# Transimpedance.net
KiCad netlist of a schematic drawn in Altium Designer
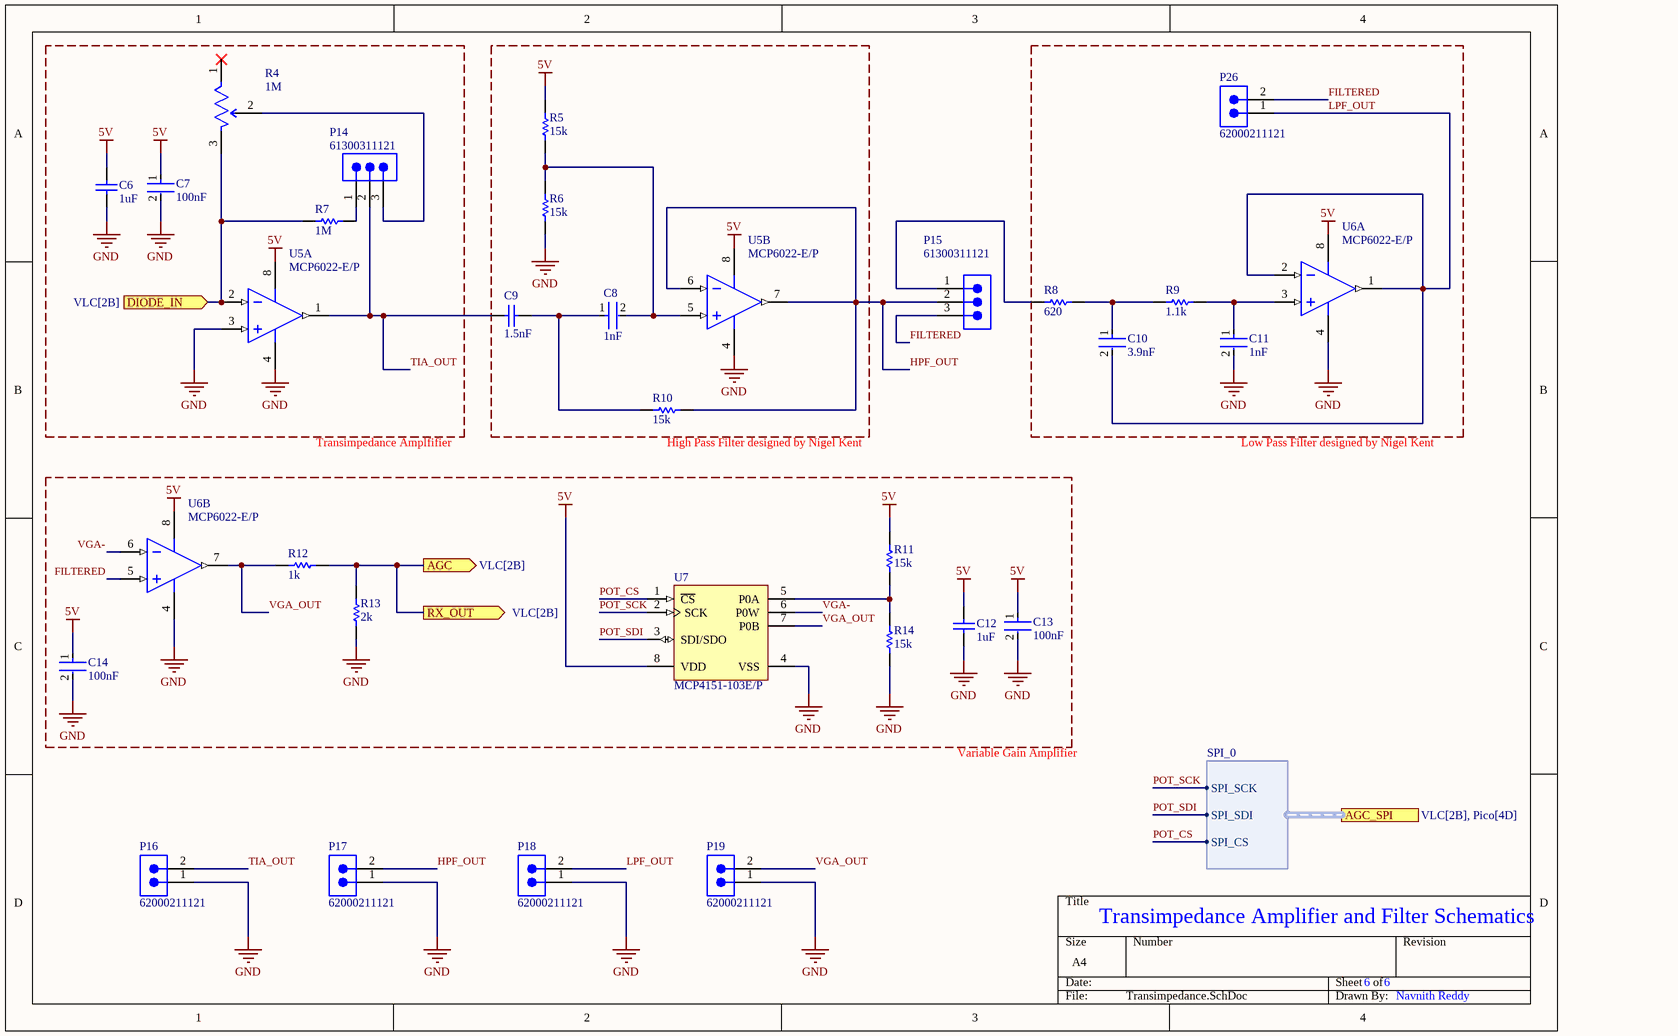
[diagram p0: Transimpedance.SchDoc]

(export (version "E")
  (design (tool "Eeschema 10.0.6"))
  (components
    (comp (ref "C6")
      (value "1uF")
      (footprint "CAPC2013X145X50LL20T25")
      (fields (field (name "MANUFACTURER") "Kemet") (field (name "PART NUMBER") "C0805C105K4PACTU"))
      (libsource (lib "Altium Content Vault") (part "CAP"))
    )
    (comp (ref "C7")
      (value "100nF")
      (footprint "FP-C0805C-DN-MFG")
      (description "CAP CER 0.1UF 16V X7R 0805")
      (fields
        (field (name "OCTOPART") "https://octopart.com/c0805c104k4ractu-kemet-92155")
        (field (name "TOLERANCE") "0.1")
      )
      (libsource (lib "Altium Content Vault") (part "b4654b650e69147ec39a6b967a45e02"))
    )
    (comp (ref "C8")
      (value "1nF")
      (footprint "FP-0805-L_2_01_0_2-W_1_25-IPC_C")
      (description "General Purpose Ceramic Capacitor, 0805, 1nF, 10%, X7R, 0.15, 50V")
      (fields (field (name "VOLTAGE") "50V") (field (name "TOLERANCE") "10%"))
      (libsource (lib "Altium Content Vault") (part "02cd4be3c70576c341d710602a673aa"))
    )
    (comp (ref "C9")
      (value "1.5nF")
      (footprint "CAPC2013X94X50ML20T25")
      (fields
        (field (name "MANUFACTURER") "AVX Interconnect / Elco")
        (field (name "PART NUMBER") "08051C152KAT2A")
      )
      (libsource (lib "Altium Content Vault") (part "CAP"))
    )
    (comp (ref "C10")
      (value "3.9nF")
      (footprint "FP-C0805C-DN-MFG")
      (description "CAP CER 3900PF 200V C0G/NP0 0805")
      (fields
        (field (name "MANUFACTURER PART NUMBER") "C0805C392J2GACAUTO")
        (field (name "OCTOPART") "https://octopart.com/c0805c392j2gacauto-kemet-46733246")
      )
      (libsource (lib "Altium Content Vault") (part "b4654b650e69147ec39a6b967a45e02"))
    )
    (comp (ref "C11")
      (value "1nF")
      (footprint "FP-0805-L_2_01_0_2-W_1_25-IPC_C")
      (description "General Purpose Ceramic Capacitor, 0805, 1nF, 10%, X7R, 0.15, 50V")
      (fields (field (name "VOLTAGE") "50V") (field (name "TOLERANCE") "10%"))
      (libsource (lib "Altium Content Vault") (part "02cd4be3c70576c341d710602a673aa"))
    )
    (comp (ref "C12")
      (value "1uF")
      (footprint "CAPC2013X145X50LL20T25")
      (fields (field (name "MANUFACTURER") "Kemet") (field (name "PART NUMBER") "C0805C105K4PACTU"))
      (libsource (lib "Altium Content Vault") (part "CAP"))
    )
    (comp (ref "C13")
      (value "100nF")
      (footprint "FP-C0805C-DN-MFG")
      (description "CAP CER 0.1UF 16V X7R 0805")
      (fields
        (field (name "OCTOPART") "https://octopart.com/c0805c104k4ractu-kemet-92155")
        (field (name "TOLERANCE") "0.1")
      )
      (libsource (lib "Altium Content Vault") (part "b4654b650e69147ec39a6b967a45e02"))
    )
    (comp (ref "C14")
      (value "100nF")
      (footprint "FP-C0805C-DN-MFG")
      (description "CAP CER 0.1UF 16V X7R 0805")
      (fields
        (field (name "OCTOPART") "https://octopart.com/c0805c104k4ractu-kemet-92155")
        (field (name "TOLERANCE") "0.1")
      )
      (libsource (lib "Altium Content Vault") (part "b4654b650e69147ec39a6b967a45e02"))
    )
    (comp (ref "P14")
      (value "61300311121")
      (footprint "61300311121")
      (libsource (lib "Altium Content Vault") (part "Header_Male_1R_03P"))
    )
    (comp (ref "P15")
      (value "61300311121")
      (footprint "61300311121")
      (libsource (lib "Altium Content Vault") (part "Header_Male_1R_03P"))
    )
    (comp (ref "P16")
      (value "62000211121")
      (footprint "62000211121")
      (libsource (lib "Altium Content Vault") (part "Header_Male_1R_02P"))
    )
    (comp (ref "P17")
      (value "62000211121")
      (footprint "62000211121")
      (libsource (lib "Altium Content Vault") (part "Header_Male_1R_02P"))
    )
    (comp (ref "P18")
      (value "62000211121")
      (footprint "62000211121")
      (libsource (lib "Altium Content Vault") (part "Header_Male_1R_02P"))
    )
    (comp (ref "P19")
      (value "62000211121")
      (footprint "62000211121")
      (libsource (lib "Altium Content Vault") (part "Header_Male_1R_02P"))
    )
    (comp (ref "P26")
      (value "62000211121")
      (footprint "62000211121")
      (libsource (lib "Altium Content Vault") (part "Header_Male_1R_02P"))
    )
    (comp (ref "R4")
      (value "1M")
      (footprint "FP-3296W-MFG")
      (description "TRIMMER 200K OHM 0.5W PC PIN TOP")
      (fields (field (name "TOLERANCE") "10%"))
      (libsource (lib "Altium Content Vault") (part "2dcfd2547301a7d3209a5e99acfd772"))
    )
    (comp (ref "R5")
      (value "15k")
      (footprint "RESC2013X55X40NL15T20")
      (fields (field (name "PART NUMBER") "TNPW080515K0BEEA") (field (name "MANUFACTURER") "Vishay Dale"))
      (libsource (lib "Altium Content Vault") (part "RES"))
    )
    (comp (ref "R6")
      (value "15k")
      (footprint "RESC2013X55X40NL15T20")
      (fields (field (name "PART NUMBER") "TNPW080515K0BEEA") (field (name "MANUFACTURER") "Vishay Dale"))
      (libsource (lib "Altium Content Vault") (part "RES"))
    )
    (comp (ref "R7")
      (value "1M")
      (footprint "RESC2013X60X40LL20T25")
      (fields (field (name "PART NUMBER") "ERA-6AEB105V") (field (name "MANUFACTURER") "Panasonic"))
      (libsource (lib "Altium Content Vault") (part "RES"))
    )
    (comp (ref "R8")
      (value "620")
      (footprint "RESC2013X70X40LL20T20")
      (fields (field (name "MANUFACTURER") "Panasonic") (field (name "PART NUMBER") "ERJ-6GEYJ621V"))
      (libsource (lib "Altium Content Vault") (part "RES"))
    )
    (comp (ref "R9")
      (value "1.1k")
      (footprint "RESC2013X50X30LL20T20")
      (fields (field (name "PART NUMBER") "CRCW08051K10FKTA") (field (name "MANUFACTURER") "Vishay Dale"))
      (libsource (lib "Altium Content Vault") (part "RES"))
    )
    (comp (ref "R10")
      (value "15k")
      (footprint "RESC2013X55X40NL15T20")
      (fields (field (name "PART NUMBER") "TNPW080515K0BEEA") (field (name "MANUFACTURER") "Vishay Dale"))
      (libsource (lib "Altium Content Vault") (part "RES"))
    )
    (comp (ref "R11")
      (value "15k")
      (footprint "RESC2013X55X40NL15T20")
      (fields (field (name "PART NUMBER") "TNPW080515K0BEEA") (field (name "MANUFACTURER") "Vishay Dale"))
      (libsource (lib "Altium Content Vault") (part "RES"))
    )
    (comp (ref "R12")
      (value "1k")
      (footprint "RESC2013X70X40ML20T20")
      (description "Chip Resistor, 1 KOhm, +/- 1%, 0.125 W, -55 to 155 degC, 0805 (2012 Metric), RoHS, Tape and Reel")
      (fields (field (name "MANUFACTURER") "Panasonic"))
      (libsource (lib "Altium Content Vault") (part "RES-2"))
    )
    (comp (ref "R13")
      (value "2k")
      (footprint "RESC2013X70X40ML20T20")
      (fields (field (name "PART NUMBER") "ERJ-6GEYJ202V") (field (name "MANUFACTURER") "Panasonic"))
      (libsource (lib "Altium Content Vault") (part "RES"))
    )
    (comp (ref "R14")
      (value "15k")
      (footprint "RESC2013X55X40NL15T20")
      (fields (field (name "PART NUMBER") "TNPW080515K0BEEA") (field (name "MANUFACTURER") "Vishay Dale"))
      (libsource (lib "Altium Content Vault") (part "RES"))
    )
    (comp (ref "U5")
      (value "MCP6022-E/P")
      (footprint "PDIP300-P8")
      (description "None")
      (libsource (lib "Altium Content Vault") (part "AMP-OPA-MCP6022-IL8"))
    )
    (comp (ref "U6")
      (value "MCP6022-E/P")
      (footprint "PDIP300-P8")
      (description "None")
      (libsource (lib "Altium Content Vault") (part "AMP-OPA-MCP6022-IL8"))
    )
    (comp (ref "U7")
      (value "MCP4151-103E/P")
      (footprint "PDIP300-P8")
      (description "7/8-Bit Single/Dual SPI Digital POT with Volatile Memory, 8-Pin PDIP, Extended Temperature")
      (libsource (lib "Altium Content Vault") (part "IN-DPOT-MCP41X1-8"))
    )
  )
  (nets
    (net (code "2") (name "/AGC") (class "Default")
      (node (ref "R12") (pin "2") (pinfunction "2_2") (pintype "passive"))
      (node (ref "R13") (pin "2") (pinfunction "2_2") (pintype "passive"))
    )
    (net (code "3") (name "/DIODE_IN") (class "Default")
      (node (ref "R4") (pin "3") (pinfunction "CW_3") (pintype "passive"))
      (node (ref "R7") (pin "1") (pinfunction "1_1") (pintype "passive"))
      (node (ref "U5") (pin "2") (pinfunction "VINA-_2") (pintype "input"))
    )
    (net (code "4") (name "/FILTERED") (class "Default")
      (node (ref "P15") (pin "3") (pinfunction "3_3") (pintype "passive"))
      (node (ref "P26") (pin "2") (pinfunction "2_2") (pintype "passive"))
      (node (ref "U6") (pin "5") (pinfunction "VINB+_5") (pintype "input"))
    )
    (net (code "5") (name "/HPF_OUT") (class "Default")
      (node (ref "P15") (pin "2") (pinfunction "2_2") (pintype "passive"))
      (node (ref "P17") (pin "2") (pinfunction "2_2") (pintype "passive"))
      (node (ref "R10") (pin "2") (pinfunction "2_2") (pintype "passive"))
      (node (ref "U5") (pin "6") (pinfunction "VINB-_6") (pintype "input"))
      (node (ref "U5") (pin "7") (pinfunction "VOUTB_7") (pintype "output"))
    )
    (net (code "6") (name "/LPF_OUT") (class "Default")
      (node (ref "C10") (pin "2") (pinfunction "2_2") (pintype "passive"))
      (node (ref "P18") (pin "2") (pinfunction "2_2") (pintype "passive"))
      (node (ref "P26") (pin "1") (pinfunction "1_1") (pintype "passive"))
      (node (ref "U6") (pin "1") (pinfunction "VOUTA_1") (pintype "output"))
      (node (ref "U6") (pin "2") (pinfunction "VINA-_2") (pintype "input"))
    )
    (net (code "7") (name "/POT_CS") (class "Default")
      (node (ref "U7") (pin "1") (pinfunction "~{CS}_1") (pintype "input"))
    )
    (net (code "8") (name "/POT_SCK") (class "Default")
      (node (ref "U7") (pin "2") (pinfunction "SCK_2") (pintype "input"))
    )
    (net (code "9") (name "/POT_SDI") (class "Default")
      (node (ref "U7") (pin "3") (pinfunction "SDI/SDO_3") (pintype "bidirectional"))
    )
    (net (code "10") (name "/TIA_OUT") (class "Default")
      (node (ref "C9") (pin "1") (pinfunction "1_1") (pintype "passive"))
      (node (ref "P14") (pin "2") (pinfunction "2_2") (pintype "passive"))
      (node (ref "P16") (pin "2") (pinfunction "2_2") (pintype "passive"))
      (node (ref "U5") (pin "1") (pinfunction "VOUTA_1") (pintype "output"))
    )
    (net (code "11") (name "/VGA-") (class "Default")
      (node (ref "U6") (pin "6") (pinfunction "VINB-_6") (pintype "input"))
      (node (ref "U7") (pin "6") (pinfunction "P0W_6") (pintype "passive"))
    )
    (net (code "12") (name "/VGA_OUT") (class "Default")
      (node (ref "P19") (pin "2") (pinfunction "2_2") (pintype "passive"))
      (node (ref "R12") (pin "1") (pinfunction "1_1") (pintype "passive"))
      (node (ref "U6") (pin "7") (pinfunction "VOUTB_7") (pintype "output"))
      (node (ref "U7") (pin "7") (pinfunction "P0B_7") (pintype "passive"))
    )
    (net (code "14") (name "5V") (class "Default")
      (node (ref "C12") (pin "2") (pinfunction "2_2") (pintype "passive"))
      (node (ref "C13") (pin "1") (pinfunction "1_1") (pintype "passive"))
      (node (ref "C14") (pin "1") (pinfunction "1_1") (pintype "passive"))
      (node (ref "C6") (pin "2") (pinfunction "2_2") (pintype "passive"))
      (node (ref "C7") (pin "1") (pinfunction "1_1") (pintype "passive"))
      (node (ref "R11") (pin "2") (pinfunction "2_2") (pintype "passive"))
      (node (ref "R5") (pin "2") (pinfunction "2_2") (pintype "passive"))
      (node (ref "U5") (pin "8") (pinfunction "VDD_8") (pintype "power_in"))
      (node (ref "U6") (pin "8") (pinfunction "VDD_8") (pintype "power_in"))
      (node (ref "U7") (pin "8") (pinfunction "VDD_8") (pintype "power_in"))
    )
    (net (code "15") (name "GND") (class "Default")
      (node (ref "C11") (pin "2") (pinfunction "2_2") (pintype "passive"))
      (node (ref "C12") (pin "1") (pinfunction "1_1") (pintype "passive"))
      (node (ref "C13") (pin "2") (pinfunction "2_2") (pintype "passive"))
      (node (ref "C14") (pin "2") (pinfunction "2_2") (pintype "passive"))
      (node (ref "C6") (pin "1") (pinfunction "1_1") (pintype "passive"))
      (node (ref "C7") (pin "2") (pinfunction "2_2") (pintype "passive"))
      (node (ref "P16") (pin "1") (pinfunction "1_1") (pintype "passive"))
      (node (ref "P17") (pin "1") (pinfunction "1_1") (pintype "passive"))
      (node (ref "P18") (pin "1") (pinfunction "1_1") (pintype "passive"))
      (node (ref "P19") (pin "1") (pinfunction "1_1") (pintype "passive"))
      (node (ref "R13") (pin "1") (pinfunction "1_1") (pintype "passive"))
      (node (ref "R14") (pin "1") (pinfunction "1_1") (pintype "passive"))
      (node (ref "R6") (pin "1") (pinfunction "1_1") (pintype "passive"))
      (node (ref "U5") (pin "3") (pinfunction "VINA+_3") (pintype "input"))
      (node (ref "U5") (pin "4") (pinfunction "VSS_4") (pintype "power_in"))
      (node (ref "U6") (pin "4") (pinfunction "VSS_4") (pintype "power_in"))
      (node (ref "U7") (pin "4") (pinfunction "VSS_4") (pintype "power_in"))
    )
    (net (code "16") (name "Net-(C8-Pad1)") (class "Default")
      (node (ref "C8") (pin "1") (pinfunction "1_1") (pintype "passive"))
      (node (ref "C9") (pin "2") (pinfunction "2_2") (pintype "passive"))
      (node (ref "R10") (pin "1") (pinfunction "1_1") (pintype "passive"))
    )
    (net (code "17") (name "Net-(C10-Pad1)") (class "Default")
      (node (ref "C10") (pin "1") (pinfunction "1_1") (pintype "passive"))
      (node (ref "R8") (pin "2") (pinfunction "2_2") (pintype "passive"))
      (node (ref "R9") (pin "1") (pinfunction "1_1") (pintype "passive"))
    )
    (net (code "18") (name "Net-(P14-Pad1)") (class "Default")
      (node (ref "P14") (pin "1") (pinfunction "1_1") (pintype "passive"))
      (node (ref "R7") (pin "2") (pinfunction "2_2") (pintype "passive"))
    )
    (net (code "19") (name "Net-(P15-Pad1)") (class "Default")
      (node (ref "P15") (pin "1") (pinfunction "1_1") (pintype "passive"))
      (node (ref "R8") (pin "1") (pinfunction "1_1") (pintype "passive"))
    )
    (net (code "20") (name "Net-(R4-WIPER)") (class "Default")
      (node (ref "P14") (pin "3") (pinfunction "3_3") (pintype "passive"))
      (node (ref "R4") (pin "2") (pinfunction "WIPER_2") (pintype "passive"))
    )
    (net (code "21") (name "Net-(U5B-VINB+)") (class "Default")
      (node (ref "C8") (pin "2") (pinfunction "2_2") (pintype "passive"))
      (node (ref "R5") (pin "1") (pinfunction "1_1") (pintype "passive"))
      (node (ref "R6") (pin "2") (pinfunction "2_2") (pintype "passive"))
      (node (ref "U5") (pin "5") (pinfunction "VINB+_5") (pintype "input"))
    )
    (net (code "22") (name "Net-(U6A-VINA+)") (class "Default")
      (node (ref "C11") (pin "1") (pinfunction "1_1") (pintype "passive"))
      (node (ref "R9") (pin "2") (pinfunction "2_2") (pintype "passive"))
      (node (ref "U6") (pin "3") (pinfunction "VINA+_3") (pintype "input"))
    )
    (net (code "23") (name "Net-(U7-P0A)") (class "Default")
      (node (ref "R11") (pin "1") (pinfunction "1_1") (pintype "passive"))
      (node (ref "R14") (pin "2") (pinfunction "2_2") (pintype "passive"))
      (node (ref "U7") (pin "5") (pinfunction "P0A_5") (pintype "passive"))
    )
    (net (code "24") (name "unconnected-(R4-CCW-Pad1)") (class "Default")
      (node (ref "R4") (pin "1") (pinfunction "CCW_1") (pintype "passive+no_connect"))
    )
  )
)
